# Fuente.net
KiCad netlist of a schematic drawn in Altium Designer
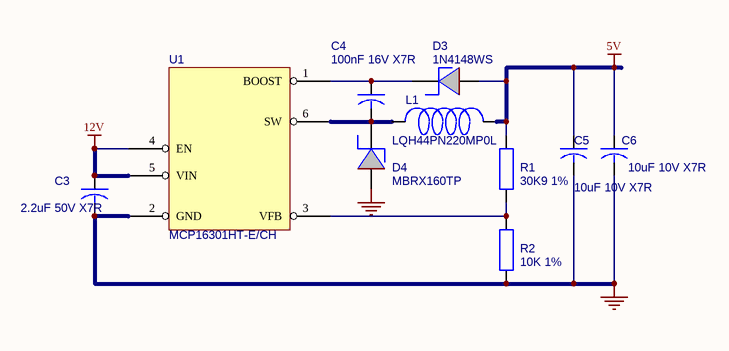
[diagram p0: Fuente.SchDoc]

(export (version "E")
  (design (tool "Eeschema 10.0.6"))
  (components
    (comp (ref "C3")
      (value "2.2uF 50V X7R")
      (footprint "C_0805")
      (description "Capacitor")
      (libsource (lib "Custom_Sch") (part "CAP"))
    )
    (comp (ref "C4")
      (value "100nF 16V X7R")
      (footprint "C_0805")
      (description "Capacitor")
      (libsource (lib "Custom_Sch") (part "CAP"))
    )
    (comp (ref "C5")
      (value "10uF 10V X7R")
      (footprint "C_0805")
      (description "Capacitor")
      (libsource (lib "Custom_Sch") (part "CAP"))
    )
    (comp (ref "C6")
      (value "10uF 10V X7R")
      (footprint "C_0805")
      (description "Capacitor")
      (libsource (lib "Custom_Sch") (part "CAP"))
    )
    (comp (ref "D3")
      (value "1N4148WS")
      (footprint "SOD_323")
      (description "Diode Shottky")
      (libsource (lib "Custom_Sch") (part "DIODO_SH"))
    )
    (comp (ref "D4")
      (value "MBRX160TP")
      (footprint "SOD_123")
      (description "Diode schottky")
      (libsource (lib "Custom_Sch") (part "DIODO_SH"))
    )
    (comp (ref "L1")
      (value "LQH44PN220MP0L")
      (footprint "VLCF5028")
      (description "Inductor")
      (libsource (lib "MVB_R00SchLib") (part "Inductor"))
    )
    (comp (ref "R1")
      (value "30K9 1%")
      (footprint "R_0805")
      (description "Resistor")
      (libsource (lib "Custom_Sch") (part "RES"))
    )
    (comp (ref "R2")
      (value "10K 1%")
      (footprint "R_0805")
      (description "Resistor")
      (libsource (lib "Custom_Sch") (part "RES"))
    )
    (comp (ref "U1")
      (value "MCP16301HT-E/CH")
      (footprint "SOT23_6P")
      (description "Buck 36V-adj 600mA SOT-6")
      (libsource (lib "Interface_SP") (part "MCP16301"))
    )
  )
  (nets
    (net (code "1") (name "5V") (class "Default")
      (node (ref "C5") (pin "1") (pinfunction "1_1") (pintype "passive"))
      (node (ref "C6") (pin "1") (pinfunction "1_1") (pintype "passive"))
      (node (ref "D3") (pin "1") (pinfunction "A_1") (pintype "passive"))
      (node (ref "L1") (pin "2") (pinfunction "2_2") (pintype "passive"))
      (node (ref "R1") (pin "2") (pinfunction "2_2") (pintype "passive"))
    )
    (net (code "2") (name "12V") (class "Default")
      (node (ref "C3") (pin "1") (pinfunction "1_1") (pintype "passive"))
      (node (ref "U1") (pin "4") (pinfunction "EN_4") (pintype "passive"))
      (node (ref "U1") (pin "5") (pinfunction "VIN_5") (pintype "passive"))
    )
    (net (code "3") (name "GND") (class "Default")
      (node (ref "C3") (pin "2") (pinfunction "2_2") (pintype "passive"))
      (node (ref "C5") (pin "2") (pinfunction "2_2") (pintype "passive"))
      (node (ref "C6") (pin "2") (pinfunction "2_2") (pintype "passive"))
      (node (ref "D4") (pin "1") (pinfunction "A_1") (pintype "passive"))
      (node (ref "R2") (pin "1") (pinfunction "1_1") (pintype "passive"))
      (node (ref "U1") (pin "2") (pinfunction "GND_2") (pintype "passive"))
    )
    (net (code "4") (name "Net-(D3-K)") (class "Default")
      (node (ref "C4") (pin "1") (pinfunction "1_1") (pintype "passive"))
      (node (ref "D3") (pin "2") (pinfunction "K_2") (pintype "passive"))
      (node (ref "U1") (pin "1") (pinfunction "BOOST_1") (pintype "passive"))
    )
    (net (code "5") (name "Net-(D4-K)") (class "Default")
      (node (ref "C4") (pin "2") (pinfunction "2_2") (pintype "passive"))
      (node (ref "D4") (pin "2") (pinfunction "K_2") (pintype "passive"))
      (node (ref "L1") (pin "1") (pinfunction "1_1") (pintype "passive"))
      (node (ref "U1") (pin "6") (pinfunction "SW_6") (pintype "passive"))
    )
    (net (code "6") (name "Net-(U1-VFB)") (class "Default")
      (node (ref "R1") (pin "1") (pinfunction "1_1") (pintype "passive"))
      (node (ref "R2") (pin "2") (pinfunction "2_2") (pintype "passive"))
      (node (ref "U1") (pin "3") (pinfunction "VFB_3") (pintype "passive"))
    )
  )
)
